# Power_Supply_Schematic.net
KiCad netlist of a schematic drawn in EAGLE
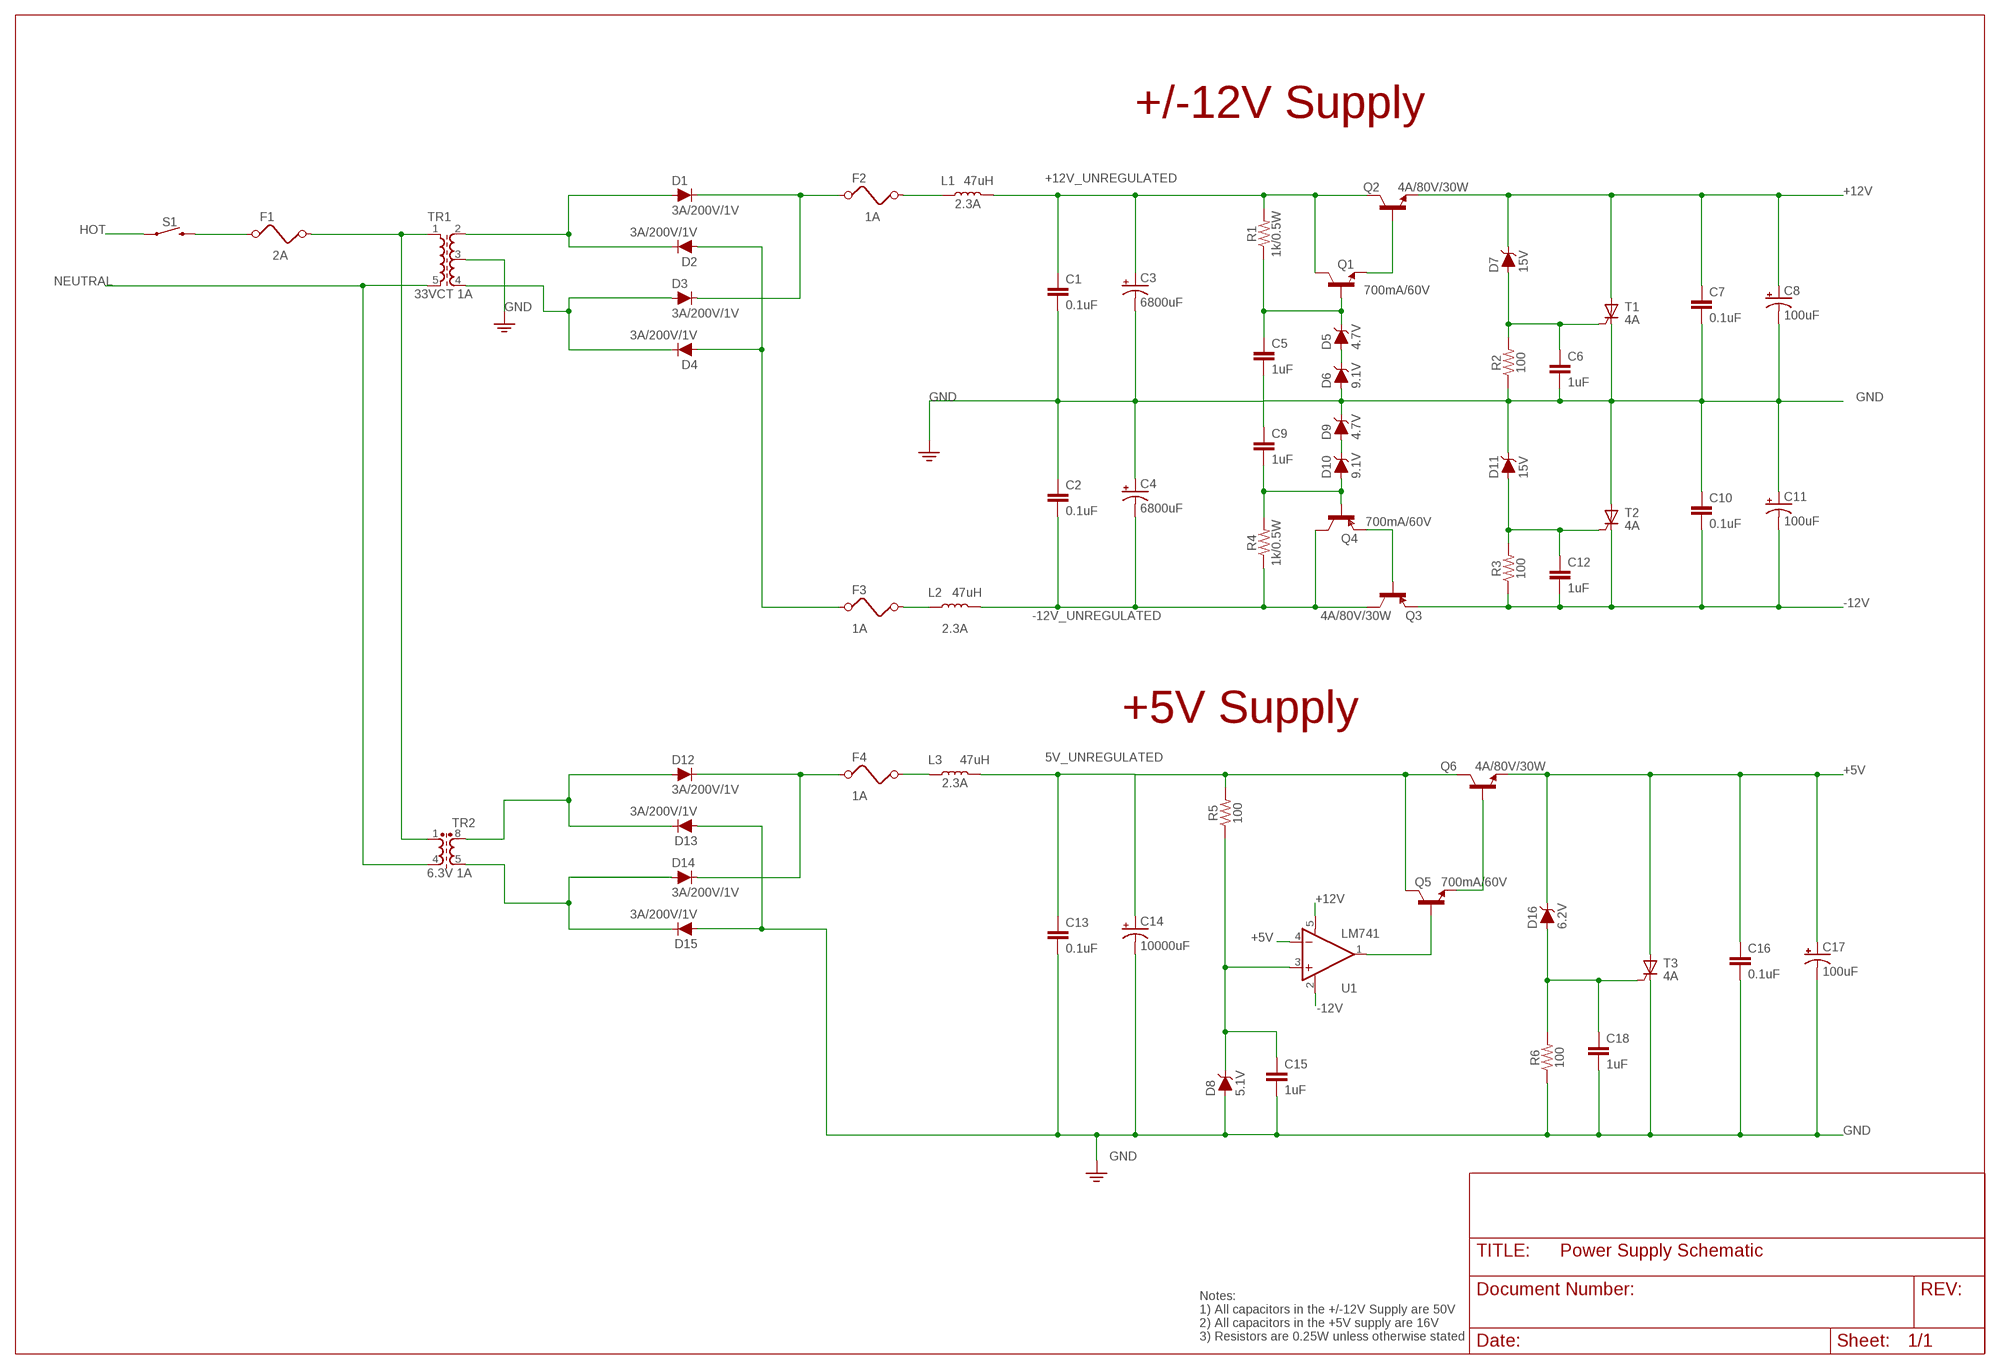
[diagram p0: schematic, sheet 1]

(export (version "E")
  (design (tool "Eeschema 10.0.6"))
  (components
    (comp (ref "C1")
      (value "0.1uF")
      (footprint "eagle-import:0402")
      (libsource (lib "eagle-import") (part "0.1UF-0402-16V-10%"))
    )
    (comp (ref "C2")
      (value "0.1uF")
      (footprint "eagle-import:0402")
      (libsource (lib "eagle-import") (part "0.1UF-0402-16V-10%"))
    )
    (comp (ref "C3")
      (value "6800uF")
      (footprint "eagle-import:NIC_10X10.5_CAP")
      (libsource (lib "eagle-import") (part "100UF-POLAR-10X10.5-63V-20%"))
    )
    (comp (ref "C4")
      (value "6800uF")
      (footprint "eagle-import:NIC_10X10.5_CAP")
      (libsource (lib "eagle-import") (part "100UF-POLAR-10X10.5-63V-20%"))
    )
    (comp (ref "C5")
      (value "1uF")
      (footprint "eagle-import:0402")
      (libsource (lib "eagle-import") (part "0.1UF-0402-16V-10%"))
    )
    (comp (ref "C6")
      (value "1uF")
      (footprint "eagle-import:0402")
      (libsource (lib "eagle-import") (part "0.1UF-0402-16V-10%"))
    )
    (comp (ref "C7")
      (value "0.1uF")
      (footprint "eagle-import:0402")
      (libsource (lib "eagle-import") (part "0.1UF-0402-16V-10%"))
    )
    (comp (ref "C8")
      (value "100uF")
      (footprint "eagle-import:NIC_10X10.5_CAP")
      (libsource (lib "eagle-import") (part "100UF-POLAR-10X10.5-63V-20%"))
    )
    (comp (ref "C9")
      (value "1uF")
      (footprint "eagle-import:0402")
      (libsource (lib "eagle-import") (part "0.1UF-0402-16V-10%"))
    )
    (comp (ref "C10")
      (value "0.1uF")
      (footprint "eagle-import:0402")
      (libsource (lib "eagle-import") (part "0.1UF-0402-16V-10%"))
    )
    (comp (ref "C11")
      (value "100uF")
      (footprint "eagle-import:NIC_10X10.5_CAP")
      (libsource (lib "eagle-import") (part "100UF-POLAR-10X10.5-63V-20%"))
    )
    (comp (ref "C12")
      (value "1uF")
      (footprint "eagle-import:0402")
      (libsource (lib "eagle-import") (part "0.1UF-0402-16V-10%"))
    )
    (comp (ref "C13")
      (value "0.1uF")
      (footprint "eagle-import:0402")
      (libsource (lib "eagle-import") (part "0.1UF-0402-16V-10%"))
    )
    (comp (ref "C14")
      (value "10000uF")
      (footprint "eagle-import:NIC_10X10.5_CAP")
      (libsource (lib "eagle-import") (part "100UF-POLAR-10X10.5-63V-20%"))
    )
    (comp (ref "C15")
      (value "1uF")
      (footprint "eagle-import:0402")
      (libsource (lib "eagle-import") (part "0.1UF-0402-16V-10%"))
    )
    (comp (ref "C16")
      (value "0.1uF")
      (footprint "eagle-import:0402")
      (libsource (lib "eagle-import") (part "0.1UF-0402-16V-10%"))
    )
    (comp (ref "C17")
      (value "100uF")
      (footprint "eagle-import:NIC_10X10.5_CAP")
      (libsource (lib "eagle-import") (part "100UF-POLAR-10X10.5-63V-20%"))
    )
    (comp (ref "C18")
      (value "1uF")
      (footprint "eagle-import:0402")
      (libsource (lib "eagle-import") (part "0.1UF-0402-16V-10%"))
    )
    (comp (ref "D1")
      (value "3A/200V/1V")
      (footprint "eagle-import:DIODE-1N4148")
      (libsource (lib "eagle-import") (part "DIODE-1N4148"))
    )
    (comp (ref "D2")
      (value "3A/200V/1V")
      (footprint "eagle-import:DIODE-1N4148")
      (libsource (lib "eagle-import") (part "DIODE-1N4148"))
    )
    (comp (ref "D3")
      (value "3A/200V/1V")
      (footprint "eagle-import:DIODE-1N4148")
      (libsource (lib "eagle-import") (part "DIODE-1N4148"))
    )
    (comp (ref "D4")
      (value "3A/200V/1V")
      (footprint "eagle-import:DIODE-1N4148")
      (libsource (lib "eagle-import") (part "DIODE-1N4148"))
    )
    (comp (ref "D5")
      (value "4.7V")
      (footprint "eagle-import:SOD-323")
      (libsource (lib "eagle-import") (part "DIODE-ZENER-BZT52C3V6S"))
    )
    (comp (ref "D6")
      (value "9.1V")
      (footprint "eagle-import:SOD-323")
      (libsource (lib "eagle-import") (part "DIODE-ZENER-BZT52C3V6S"))
    )
    (comp (ref "D7")
      (value "15V")
      (footprint "eagle-import:SOD-323")
      (libsource (lib "eagle-import") (part "DIODE-ZENER-BZT52C3V6S"))
    )
    (comp (ref "D8")
      (value "5.1V")
      (footprint "eagle-import:SOD-323")
      (libsource (lib "eagle-import") (part "DIODE-ZENER-BZT52C3V6S"))
    )
    (comp (ref "D9")
      (value "4.7V")
      (footprint "eagle-import:SOD-323")
      (libsource (lib "eagle-import") (part "DIODE-ZENER-BZT52C3V6S"))
    )
    (comp (ref "D10")
      (value "9.1V")
      (footprint "eagle-import:SOD-323")
      (libsource (lib "eagle-import") (part "DIODE-ZENER-BZT52C3V6S"))
    )
    (comp (ref "D11")
      (value "15V")
      (footprint "eagle-import:SOD-323")
      (libsource (lib "eagle-import") (part "DIODE-ZENER-BZT52C3V6S"))
    )
    (comp (ref "D12")
      (value "3A/200V/1V")
      (footprint "eagle-import:DIODE-1N4148")
      (libsource (lib "eagle-import") (part "DIODE-1N4148"))
    )
    (comp (ref "D13")
      (value "3A/200V/1V")
      (footprint "eagle-import:DIODE-1N4148")
      (libsource (lib "eagle-import") (part "DIODE-1N4148"))
    )
    (comp (ref "D14")
      (value "3A/200V/1V")
      (footprint "eagle-import:DIODE-1N4148")
      (libsource (lib "eagle-import") (part "DIODE-1N4148"))
    )
    (comp (ref "D15")
      (value "3A/200V/1V")
      (footprint "eagle-import:DIODE-1N4148")
      (libsource (lib "eagle-import") (part "DIODE-1N4148"))
    )
    (comp (ref "D16")
      (value "6.2V")
      (footprint "eagle-import:SOD-323")
      (libsource (lib "eagle-import") (part "DIODE-ZENER-BZT52C3V6S"))
    )
    (comp (ref "F1")
      (value "FUSE")
      (footprint "eagle-import:FUSE")
      (libsource (lib "eagle-import") (part "FUSE"))
    )
    (comp (ref "F2")
      (value "FUSE")
      (footprint "eagle-import:FUSE")
      (libsource (lib "eagle-import") (part "FUSE"))
    )
    (comp (ref "F3")
      (value "FUSE")
      (footprint "eagle-import:FUSE")
      (libsource (lib "eagle-import") (part "FUSE"))
    )
    (comp (ref "F4")
      (value "FUSE")
      (footprint "eagle-import:FUSE")
      (libsource (lib "eagle-import") (part "FUSE"))
    )
    (comp (ref "L1")
      (value "47uH")
      (footprint "eagle-import:0402")
      (libsource (lib "eagle-import") (part "INDUCTOR-0402-3.9NH"))
    )
    (comp (ref "L2")
      (value "47uH")
      (footprint "eagle-import:0402")
      (libsource (lib "eagle-import") (part "INDUCTOR-0402-3.9NH"))
    )
    (comp (ref "L3")
      (value "47uH")
      (footprint "eagle-import:0402")
      (libsource (lib "eagle-import") (part "INDUCTOR-0402-3.9NH"))
    )
    (comp (ref "Q1")
      (value "700mA/60V")
      (footprint "eagle-import:TO-92")
      (libsource (lib "eagle-import") (part "TRANS_NPN-2N3904"))
    )
    (comp (ref "Q2")
      (value "4A/80V/30W")
      (footprint "eagle-import:TO-92")
      (libsource (lib "eagle-import") (part "TRANS_NPN-2N3904"))
    )
    (comp (ref "Q3")
      (value "4A/80V/30W")
      (footprint "eagle-import:SOT23-3")
      (libsource (lib "eagle-import") (part "TRANS_PNP-PMBT3906|MMBT3906L"))
    )
    (comp (ref "Q4")
      (value "700mA/60V")
      (footprint "eagle-import:SOT23-3")
      (libsource (lib "eagle-import") (part "TRANS_PNP-PMBT3906|MMBT3906L"))
    )
    (comp (ref "Q5")
      (value "700mA/60V")
      (footprint "eagle-import:TO-92")
      (libsource (lib "eagle-import") (part "TRANS_NPN-2N3904"))
    )
    (comp (ref "Q6")
      (value "4A/80V/30W")
      (footprint "eagle-import:TO-92")
      (libsource (lib "eagle-import") (part "TRANS_NPN-2N3904"))
    )
    (comp (ref "R1")
      (value "1k/0.5W")
      (footprint "eagle-import:2010")
      (libsource (lib "eagle-import") (part "0.11OHM-2010-1/2W-1%"))
    )
    (comp (ref "R2")
      (value "100")
      (footprint "eagle-import:2010")
      (libsource (lib "eagle-import") (part "0.11OHM-2010-1/2W-1%"))
    )
    (comp (ref "R3")
      (value "100")
      (footprint "eagle-import:2010")
      (libsource (lib "eagle-import") (part "0.11OHM-2010-1/2W-1%"))
    )
    (comp (ref "R4")
      (value "1k/0.5W")
      (footprint "eagle-import:2010")
      (libsource (lib "eagle-import") (part "0.11OHM-2010-1/2W-1%"))
    )
    (comp (ref "R5")
      (value "100")
      (footprint "eagle-import:2010")
      (libsource (lib "eagle-import") (part "0.11OHM-2010-1/2W-1%"))
    )
    (comp (ref "R6")
      (value "100")
      (footprint "eagle-import:2010")
      (libsource (lib "eagle-import") (part "0.11OHM-2010-1/2W-1%"))
    )
    (comp (ref "S1")
      (value "MOMENTARY-SWITCH-SPST-PTH-6.0MM")
      (footprint "eagle-import:TACTILE_SWITCH_PTH_6.0MM")
      (libsource (lib "eagle-import") (part "MOMENTARY-SWITCH-SPST-PTH-6.0MM"))
    )
    (comp (ref "T1")
      (value "BRX44")
      (footprint "eagle-import:SOT54")
      (libsource (lib "eagle-import") (part "BRX44"))
    )
    (comp (ref "T2")
      (value "BRX44")
      (footprint "eagle-import:SOT54")
      (libsource (lib "eagle-import") (part "BRX44"))
    )
    (comp (ref "T3")
      (value "BRX44")
      (footprint "eagle-import:SOT54")
      (libsource (lib "eagle-import") (part "BRX44"))
    )
    (comp (ref "TR1")
      (value "MS40A")
      (footprint "eagle-import:MS40")
      (libsource (lib "eagle-import") (part "MS40A"))
    )
    (comp (ref "TR2")
      (value "SMR6-2W")
      (footprint "eagle-import:SM-R6")
      (libsource (lib "eagle-import") (part "SMR6-2W"))
    )
    (comp (ref "U1")
      (value "LM741")
      (footprint "eagle-import:SOT23-5")
      (libsource (lib "eagle-import") (part "MCP6291T-E/OT"))
    )
  )
  (nets
    (net (code "1") (name "/+5V") (class "Default")
      (node (ref "C16") (pin "1") (pinfunction "1_1") (pintype "passive"))
      (node (ref "C17") (pin "+") (pinfunction "+_+") (pintype "passive"))
      (node (ref "D16") (pin "C") (pinfunction "C_C") (pintype "passive"))
      (node (ref "Q6") (pin "1") (pinfunction "E_1") (pintype "passive"))
      (node (ref "T3") (pin "A") (pinfunction "A_A") (pintype "passive"))
      (node (ref "U1") (pin "4") (pinfunction "-IN_4") (pintype "input"))
    )
    (net (code "2") (name "/+12V") (class "Default")
      (node (ref "C7") (pin "1") (pinfunction "1_1") (pintype "passive"))
      (node (ref "C8") (pin "+") (pinfunction "+_+") (pintype "passive"))
      (node (ref "D7") (pin "C") (pinfunction "C_C") (pintype "passive"))
      (node (ref "Q2") (pin "1") (pinfunction "E_1") (pintype "passive"))
      (node (ref "T1") (pin "A") (pinfunction "A_A") (pintype "passive"))
      (node (ref "U1") (pin "5") (pinfunction "V+_5") (pintype "power_in"))
    )
    (net (code "3") (name "/+12V_UNREGULATED") (class "Default")
      (node (ref "C1") (pin "1") (pinfunction "1_1") (pintype "passive"))
      (node (ref "C3") (pin "+") (pinfunction "+_+") (pintype "passive"))
      (node (ref "L1") (pin "2") (pinfunction "2_2") (pintype "passive"))
      (node (ref "Q1") (pin "3") (pinfunction "C_3") (pintype "passive"))
      (node (ref "Q2") (pin "3") (pinfunction "C_3") (pintype "passive"))
      (node (ref "R1") (pin "2") (pinfunction "2_2") (pintype "passive"))
    )
    (net (code "4") (name "/-12V") (class "Default")
      (node (ref "C10") (pin "2") (pinfunction "2_2") (pintype "passive"))
      (node (ref "C11") (pin "-") (pinfunction "-_-") (pintype "passive"))
      (node (ref "C12") (pin "2") (pinfunction "2_2") (pintype "passive"))
      (node (ref "Q3") (pin "2") (pinfunction "E_2") (pintype "passive"))
      (node (ref "R3") (pin "1") (pinfunction "1_1") (pintype "passive"))
      (node (ref "T2") (pin "C") (pinfunction "C_C") (pintype "passive"))
      (node (ref "U1") (pin "2") (pinfunction "V-_2") (pintype "power_in"))
    )
    (net (code "5") (name "/-12V_UNREGULATED") (class "Default")
      (node (ref "C2") (pin "2") (pinfunction "2_2") (pintype "passive"))
      (node (ref "C4") (pin "-") (pinfunction "-_-") (pintype "passive"))
      (node (ref "L2") (pin "2") (pinfunction "2_2") (pintype "passive"))
      (node (ref "Q3") (pin "3") (pinfunction "C_3") (pintype "passive"))
      (node (ref "Q4") (pin "3") (pinfunction "C_3") (pintype "passive"))
      (node (ref "R4") (pin "1") (pinfunction "1_1") (pintype "passive"))
    )
    (net (code "6") (name "/5V_UNREGULATED") (class "Default")
      (node (ref "C13") (pin "1") (pinfunction "1_1") (pintype "passive"))
      (node (ref "C14") (pin "+") (pinfunction "+_+") (pintype "passive"))
      (node (ref "L3") (pin "2") (pinfunction "2_2") (pintype "passive"))
      (node (ref "Q5") (pin "3") (pinfunction "C_3") (pintype "passive"))
      (node (ref "Q6") (pin "3") (pinfunction "C_3") (pintype "passive"))
      (node (ref "R5") (pin "2") (pinfunction "2_2") (pintype "passive"))
    )
    (net (code "7") (name "/HOT") (class "Default")
      (node (ref "S1") (pin "1") (pinfunction "1_1") (pintype "passive"))
    )
    (net (code "8") (name "/NEUTRAL") (class "Default")
      (node (ref "TR1") (pin "5") (pinfunction "5_5") (pintype "passive"))
      (node (ref "TR2") (pin "4") (pinfunction "4_4") (pintype "passive"))
    )
    (net (code "9") (name "GND2") (class "Default")
      (node (ref "C1") (pin "2") (pinfunction "2_2") (pintype "passive"))
      (node (ref "C10") (pin "1") (pinfunction "1_1") (pintype "passive"))
      (node (ref "C11") (pin "+") (pinfunction "+_+") (pintype "passive"))
      (node (ref "C13") (pin "2") (pinfunction "2_2") (pintype "passive"))
      (node (ref "C14") (pin "-") (pinfunction "-_-") (pintype "passive"))
      (node (ref "C15") (pin "2") (pinfunction "2_2") (pintype "passive"))
      (node (ref "C16") (pin "2") (pinfunction "2_2") (pintype "passive"))
      (node (ref "C17") (pin "-") (pinfunction "-_-") (pintype "passive"))
      (node (ref "C18") (pin "2") (pinfunction "2_2") (pintype "passive"))
      (node (ref "C2") (pin "1") (pinfunction "1_1") (pintype "passive"))
      (node (ref "C3") (pin "-") (pinfunction "-_-") (pintype "passive"))
      (node (ref "C4") (pin "+") (pinfunction "+_+") (pintype "passive"))
      (node (ref "C5") (pin "2") (pinfunction "2_2") (pintype "passive"))
      (node (ref "C6") (pin "2") (pinfunction "2_2") (pintype "passive"))
      (node (ref "C7") (pin "2") (pinfunction "2_2") (pintype "passive"))
      (node (ref "C8") (pin "-") (pinfunction "-_-") (pintype "passive"))
      (node (ref "C9") (pin "1") (pinfunction "1_1") (pintype "passive"))
      (node (ref "D11") (pin "C") (pinfunction "C_C") (pintype "passive"))
      (node (ref "D13") (pin "A") (pinfunction "A_A") (pintype "passive"))
      (node (ref "D15") (pin "A") (pinfunction "A_A") (pintype "passive"))
      (node (ref "D6") (pin "A") (pinfunction "A_A") (pintype "passive"))
      (node (ref "D8") (pin "A") (pinfunction "A_A") (pintype "passive"))
      (node (ref "D9") (pin "C") (pinfunction "C_C") (pintype "passive"))
      (node (ref "R2") (pin "1") (pinfunction "1_1") (pintype "passive"))
      (node (ref "R6") (pin "1") (pinfunction "1_1") (pintype "passive"))
      (node (ref "T1") (pin "C") (pinfunction "C_C") (pintype "passive"))
      (node (ref "T2") (pin "A") (pinfunction "A_A") (pintype "passive"))
      (node (ref "T3") (pin "C") (pinfunction "C_C") (pintype "passive"))
      (node (ref "TR1") (pin "3") (pinfunction "3_3") (pintype "passive"))
    )
    (net (code "10") (name "Net-(C6-Pad1)") (class "Default")
      (node (ref "C6") (pin "1") (pinfunction "1_1") (pintype "passive"))
      (node (ref "D7") (pin "A") (pinfunction "A_A") (pintype "passive"))
      (node (ref "R2") (pin "2") (pinfunction "2_2") (pintype "passive"))
      (node (ref "T1") (pin "G") (pinfunction "G_G") (pintype "passive"))
    )
    (net (code "11") (name "Net-(C12-Pad1)") (class "Default")
      (node (ref "C12") (pin "1") (pinfunction "1_1") (pintype "passive"))
      (node (ref "D11") (pin "A") (pinfunction "A_A") (pintype "passive"))
      (node (ref "R3") (pin "2") (pinfunction "2_2") (pintype "passive"))
      (node (ref "T2") (pin "G") (pinfunction "G_G") (pintype "passive"))
    )
    (net (code "12") (name "Net-(C18-Pad1)") (class "Default")
      (node (ref "C18") (pin "1") (pinfunction "1_1") (pintype "passive"))
      (node (ref "D16") (pin "A") (pinfunction "A_A") (pintype "passive"))
      (node (ref "R6") (pin "2") (pinfunction "2_2") (pintype "passive"))
      (node (ref "T3") (pin "G") (pinfunction "G_G") (pintype "passive"))
    )
    (net (code "13") (name "Net-(D1-PadA)") (class "Default")
      (node (ref "D1") (pin "A") (pinfunction "A_A") (pintype "passive"))
      (node (ref "D2") (pin "C") (pinfunction "C_C") (pintype "passive"))
      (node (ref "TR1") (pin "2") (pinfunction "2_2") (pintype "passive"))
    )
    (net (code "14") (name "Net-(D1-PadC)") (class "Default")
      (node (ref "D1") (pin "C") (pinfunction "C_C") (pintype "passive"))
      (node (ref "D3") (pin "C") (pinfunction "C_C") (pintype "passive"))
      (node (ref "F2") (pin "1") (pinfunction "1_1") (pintype "passive"))
    )
    (net (code "15") (name "Net-(D2-PadA)") (class "Default")
      (node (ref "D2") (pin "A") (pinfunction "A_A") (pintype "passive"))
      (node (ref "D4") (pin "A") (pinfunction "A_A") (pintype "passive"))
      (node (ref "F3") (pin "1") (pinfunction "1_1") (pintype "passive"))
    )
    (net (code "16") (name "Net-(D3-PadA)") (class "Default")
      (node (ref "D3") (pin "A") (pinfunction "A_A") (pintype "passive"))
      (node (ref "D4") (pin "C") (pinfunction "C_C") (pintype "passive"))
      (node (ref "TR1") (pin "4") (pinfunction "4_4") (pintype "passive"))
    )
    (net (code "17") (name "Net-(D5-PadA)") (class "Default")
      (node (ref "D5") (pin "A") (pinfunction "A_A") (pintype "passive"))
      (node (ref "D6") (pin "C") (pinfunction "C_C") (pintype "passive"))
    )
    (net (code "18") (name "Net-(D10-PadC)") (class "Default")
      (node (ref "D10") (pin "C") (pinfunction "C_C") (pintype "passive"))
      (node (ref "D9") (pin "A") (pinfunction "A_A") (pintype "passive"))
    )
    (net (code "19") (name "Net-(D12-PadA)") (class "Default")
      (node (ref "D12") (pin "A") (pinfunction "A_A") (pintype "passive"))
      (node (ref "D13") (pin "C") (pinfunction "C_C") (pintype "passive"))
      (node (ref "TR2") (pin "8") (pinfunction "8_8") (pintype "passive"))
    )
    (net (code "20") (name "Net-(D12-PadC)") (class "Default")
      (node (ref "D12") (pin "C") (pinfunction "C_C") (pintype "passive"))
      (node (ref "D14") (pin "C") (pinfunction "C_C") (pintype "passive"))
      (node (ref "F4") (pin "1") (pinfunction "1_1") (pintype "passive"))
    )
    (net (code "21") (name "Net-(D14-PadA)") (class "Default")
      (node (ref "D14") (pin "A") (pinfunction "A_A") (pintype "passive"))
      (node (ref "D15") (pin "C") (pinfunction "C_C") (pintype "passive"))
      (node (ref "TR2") (pin "5") (pinfunction "5_5") (pintype "passive"))
    )
    (net (code "22") (name "Net-(F1-Pad2)") (class "Default")
      (node (ref "F1") (pin "2") (pinfunction "2_2") (pintype "passive"))
      (node (ref "TR1") (pin "1") (pinfunction "1_1") (pintype "passive"))
      (node (ref "TR2") (pin "1") (pinfunction "1_1") (pintype "passive"))
    )
    (net (code "23") (name "Net-(F2-Pad2)") (class "Default")
      (node (ref "F2") (pin "2") (pinfunction "2_2") (pintype "passive"))
      (node (ref "L1") (pin "1") (pinfunction "1_1") (pintype "passive"))
    )
    (net (code "24") (name "Net-(F3-Pad2)") (class "Default")
      (node (ref "F3") (pin "2") (pinfunction "2_2") (pintype "passive"))
      (node (ref "L2") (pin "1") (pinfunction "1_1") (pintype "passive"))
    )
    (net (code "25") (name "Net-(F4-Pad2)") (class "Default")
      (node (ref "F4") (pin "2") (pinfunction "2_2") (pintype "passive"))
      (node (ref "L3") (pin "1") (pinfunction "1_1") (pintype "passive"))
    )
    (net (code "26") (name "Net-(Q1-B)") (class "Default")
      (node (ref "C5") (pin "1") (pinfunction "1_1") (pintype "passive"))
      (node (ref "D5") (pin "C") (pinfunction "C_C") (pintype "passive"))
      (node (ref "Q1") (pin "2") (pinfunction "B_2") (pintype "passive"))
      (node (ref "R1") (pin "1") (pinfunction "1_1") (pintype "passive"))
    )
    (net (code "27") (name "Net-(Q1-E)") (class "Default")
      (node (ref "Q1") (pin "1") (pinfunction "E_1") (pintype "passive"))
      (node (ref "Q2") (pin "2") (pinfunction "B_2") (pintype "passive"))
    )
    (net (code "28") (name "Net-(Q3-B)") (class "Default")
      (node (ref "Q3") (pin "1") (pinfunction "B_1") (pintype "passive"))
      (node (ref "Q4") (pin "2") (pinfunction "E_2") (pintype "passive"))
    )
    (net (code "29") (name "Net-(Q4-B)") (class "Default")
      (node (ref "C9") (pin "2") (pinfunction "2_2") (pintype "passive"))
      (node (ref "D10") (pin "A") (pinfunction "A_A") (pintype "passive"))
      (node (ref "Q4") (pin "1") (pinfunction "B_1") (pintype "passive"))
      (node (ref "R4") (pin "2") (pinfunction "2_2") (pintype "passive"))
    )
    (net (code "30") (name "Net-(Q5-B)") (class "Default")
      (node (ref "Q5") (pin "2") (pinfunction "B_2") (pintype "passive"))
      (node (ref "U1") (pin "1") (pinfunction "OUT_1") (pintype "output"))
    )
    (net (code "31") (name "Net-(Q5-E)") (class "Default")
      (node (ref "Q5") (pin "1") (pinfunction "E_1") (pintype "passive"))
      (node (ref "Q6") (pin "2") (pinfunction "B_2") (pintype "passive"))
    )
    (net (code "32") (name "Net-(S1-2)") (class "Default")
      (node (ref "F1") (pin "1") (pinfunction "1_1") (pintype "passive"))
      (node (ref "S1") (pin "3") (pinfunction "2_3") (pintype "passive"))
    )
    (net (code "33") (name "Net-(U1-+IN)") (class "Default")
      (node (ref "C15") (pin "1") (pinfunction "1_1") (pintype "passive"))
      (node (ref "D8") (pin "C") (pinfunction "C_C") (pintype "passive"))
      (node (ref "R5") (pin "1") (pinfunction "1_1") (pintype "passive"))
      (node (ref "U1") (pin "3") (pinfunction "+IN_3") (pintype "input"))
    )
  )
)
